# Nghich.net
KiCad netlist of a schematic drawn in Altium Designer
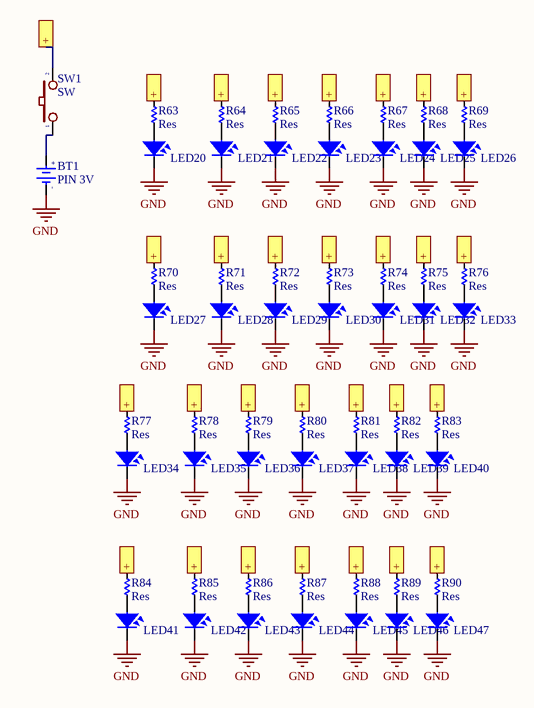
[diagram p0: Nghich.SchDoc]

(export (version "E")
  (design (tool "Eeschema 10.0.6"))
  (components
    (comp (ref "BT1")
      (value "PIN 3V")
      (footprint "PIN3V")
      (description "Battery 3VDC")
      (libsource (lib "LIBRARY") (part "PIN 3V"))
    )
    (comp (ref "LED20")
      (value "LED")
      (footprint "LED-0805-Blue")
      (libsource (lib "LIBRARY") (part "LED SMD"))
    )
    (comp (ref "LED21")
      (value "LED")
      (footprint "LED-0805-Blue")
      (libsource (lib "LIBRARY") (part "LED SMD"))
    )
    (comp (ref "LED22")
      (value "LED")
      (footprint "LED-0805-Blue")
      (libsource (lib "LIBRARY") (part "LED SMD"))
    )
    (comp (ref "LED23")
      (value "LED")
      (footprint "LED-0805-Blue")
      (libsource (lib "LIBRARY") (part "LED SMD"))
    )
    (comp (ref "LED24")
      (value "LED")
      (footprint "LED-0805-Blue")
      (libsource (lib "LIBRARY") (part "LED SMD"))
    )
    (comp (ref "LED25")
      (value "LED")
      (footprint "LED-0805-Blue")
      (libsource (lib "LIBRARY") (part "LED SMD"))
    )
    (comp (ref "LED26")
      (value "LED")
      (footprint "LED-0805-Blue")
      (libsource (lib "LIBRARY") (part "LED SMD"))
    )
    (comp (ref "LED27")
      (value "LED")
      (footprint "LED-0805-Blue")
      (libsource (lib "LIBRARY") (part "LED SMD"))
    )
    (comp (ref "LED28")
      (value "LED")
      (footprint "LED-0805-Blue")
      (libsource (lib "LIBRARY") (part "LED SMD"))
    )
    (comp (ref "LED29")
      (value "LED")
      (footprint "LED-0805-Blue")
      (libsource (lib "LIBRARY") (part "LED SMD"))
    )
    (comp (ref "LED30")
      (value "LED")
      (footprint "LED-0805-Blue")
      (libsource (lib "LIBRARY") (part "LED SMD"))
    )
    (comp (ref "LED31")
      (value "LED")
      (footprint "LED-0805-Blue")
      (libsource (lib "LIBRARY") (part "LED SMD"))
    )
    (comp (ref "LED32")
      (value "LED")
      (footprint "LED-0805-Blue")
      (libsource (lib "LIBRARY") (part "LED SMD"))
    )
    (comp (ref "LED33")
      (value "LED")
      (footprint "LED-0805-Blue")
      (libsource (lib "LIBRARY") (part "LED SMD"))
    )
    (comp (ref "LED34")
      (value "LED")
      (footprint "LED-0805-Blue")
      (libsource (lib "LIBRARY") (part "LED SMD"))
    )
    (comp (ref "LED35")
      (value "LED")
      (footprint "LED-0805-Blue")
      (libsource (lib "LIBRARY") (part "LED SMD"))
    )
    (comp (ref "LED36")
      (value "LED")
      (footprint "LED-0805-Blue")
      (libsource (lib "LIBRARY") (part "LED SMD"))
    )
    (comp (ref "LED37")
      (value "LED")
      (footprint "LED-0805-Blue")
      (libsource (lib "LIBRARY") (part "LED SMD"))
    )
    (comp (ref "LED38")
      (value "LED")
      (footprint "LED-0805-Blue")
      (libsource (lib "LIBRARY") (part "LED SMD"))
    )
    (comp (ref "LED39")
      (value "LED")
      (footprint "LED-0805-Blue")
      (libsource (lib "LIBRARY") (part "LED SMD"))
    )
    (comp (ref "LED40")
      (value "LED")
      (footprint "LED-0805-Blue")
      (libsource (lib "LIBRARY") (part "LED SMD"))
    )
    (comp (ref "LED41")
      (value "LED")
      (footprint "LED-0805-Blue")
      (libsource (lib "LIBRARY") (part "LED SMD"))
    )
    (comp (ref "LED42")
      (value "LED")
      (footprint "LED-0805-Blue")
      (libsource (lib "LIBRARY") (part "LED SMD"))
    )
    (comp (ref "LED43")
      (value "LED")
      (footprint "LED-0805-Blue")
      (libsource (lib "LIBRARY") (part "LED SMD"))
    )
    (comp (ref "LED44")
      (value "LED")
      (footprint "LED-0805-Blue")
      (libsource (lib "LIBRARY") (part "LED SMD"))
    )
    (comp (ref "LED45")
      (value "LED")
      (footprint "LED-0805-Blue")
      (libsource (lib "LIBRARY") (part "LED SMD"))
    )
    (comp (ref "LED46")
      (value "LED")
      (footprint "LED-0805-Blue")
      (libsource (lib "LIBRARY") (part "LED SMD"))
    )
    (comp (ref "LED47")
      (value "LED")
      (footprint "LED-0805-Blue")
      (libsource (lib "LIBRARY") (part "LED SMD"))
    )
    (comp (ref "R63")
      (value "Res")
      (footprint "RES-SMD-0805")
      (description "Resistor")
      (fields
        (field (name "MANUFACTURER") "Generic Components")
        (field (name "PUBLISHER") "Altium Hobart Technology Centre")
      )
      (libsource (lib "LIBRARY") (part "Res-SMD"))
    )
    (comp (ref "R64")
      (value "Res")
      (footprint "RES-SMD-0805")
      (description "Resistor")
      (fields
        (field (name "MANUFACTURER") "Generic Components")
        (field (name "PUBLISHER") "Altium Hobart Technology Centre")
      )
      (libsource (lib "LIBRARY") (part "Res-SMD"))
    )
    (comp (ref "R65")
      (value "Res")
      (footprint "RES-SMD-0805")
      (description "Resistor")
      (fields
        (field (name "MANUFACTURER") "Generic Components")
        (field (name "PUBLISHER") "Altium Hobart Technology Centre")
      )
      (libsource (lib "LIBRARY") (part "Res-SMD"))
    )
    (comp (ref "R66")
      (value "Res")
      (footprint "RES-SMD-0805")
      (description "Resistor")
      (fields
        (field (name "MANUFACTURER") "Generic Components")
        (field (name "PUBLISHER") "Altium Hobart Technology Centre")
      )
      (libsource (lib "LIBRARY") (part "Res-SMD"))
    )
    (comp (ref "R67")
      (value "Res")
      (footprint "RES-SMD-0805")
      (description "Resistor")
      (fields
        (field (name "MANUFACTURER") "Generic Components")
        (field (name "PUBLISHER") "Altium Hobart Technology Centre")
      )
      (libsource (lib "LIBRARY") (part "Res-SMD"))
    )
    (comp (ref "R68")
      (value "Res")
      (footprint "RES-SMD-0805")
      (description "Resistor")
      (fields
        (field (name "MANUFACTURER") "Generic Components")
        (field (name "PUBLISHER") "Altium Hobart Technology Centre")
      )
      (libsource (lib "LIBRARY") (part "Res-SMD"))
    )
    (comp (ref "R69")
      (value "Res")
      (footprint "RES-SMD-0805")
      (description "Resistor")
      (fields
        (field (name "MANUFACTURER") "Generic Components")
        (field (name "PUBLISHER") "Altium Hobart Technology Centre")
      )
      (libsource (lib "LIBRARY") (part "Res-SMD"))
    )
    (comp (ref "R70")
      (value "Res")
      (footprint "RES-SMD-0805")
      (description "Resistor")
      (fields
        (field (name "MANUFACTURER") "Generic Components")
        (field (name "PUBLISHER") "Altium Hobart Technology Centre")
      )
      (libsource (lib "LIBRARY") (part "Res-SMD"))
    )
    (comp (ref "R71")
      (value "Res")
      (footprint "RES-SMD-0805")
      (description "Resistor")
      (fields
        (field (name "MANUFACTURER") "Generic Components")
        (field (name "PUBLISHER") "Altium Hobart Technology Centre")
      )
      (libsource (lib "LIBRARY") (part "Res-SMD"))
    )
    (comp (ref "R72")
      (value "Res")
      (footprint "RES-SMD-0805")
      (description "Resistor")
      (fields
        (field (name "MANUFACTURER") "Generic Components")
        (field (name "PUBLISHER") "Altium Hobart Technology Centre")
      )
      (libsource (lib "LIBRARY") (part "Res-SMD"))
    )
    (comp (ref "R73")
      (value "Res")
      (footprint "RES-SMD-0805")
      (description "Resistor")
      (fields
        (field (name "MANUFACTURER") "Generic Components")
        (field (name "PUBLISHER") "Altium Hobart Technology Centre")
      )
      (libsource (lib "LIBRARY") (part "Res-SMD"))
    )
    (comp (ref "R74")
      (value "Res")
      (footprint "RES-SMD-0805")
      (description "Resistor")
      (fields
        (field (name "MANUFACTURER") "Generic Components")
        (field (name "PUBLISHER") "Altium Hobart Technology Centre")
      )
      (libsource (lib "LIBRARY") (part "Res-SMD"))
    )
    (comp (ref "R75")
      (value "Res")
      (footprint "RES-SMD-0805")
      (description "Resistor")
      (fields
        (field (name "MANUFACTURER") "Generic Components")
        (field (name "PUBLISHER") "Altium Hobart Technology Centre")
      )
      (libsource (lib "LIBRARY") (part "Res-SMD"))
    )
    (comp (ref "R76")
      (value "Res")
      (footprint "RES-SMD-0805")
      (description "Resistor")
      (fields
        (field (name "MANUFACTURER") "Generic Components")
        (field (name "PUBLISHER") "Altium Hobart Technology Centre")
      )
      (libsource (lib "LIBRARY") (part "Res-SMD"))
    )
    (comp (ref "R77")
      (value "Res")
      (footprint "RES-SMD-0805")
      (description "Resistor")
      (fields
        (field (name "MANUFACTURER") "Generic Components")
        (field (name "PUBLISHER") "Altium Hobart Technology Centre")
      )
      (libsource (lib "LIBRARY") (part "Res-SMD"))
    )
    (comp (ref "R78")
      (value "Res")
      (footprint "RES-SMD-0805")
      (description "Resistor")
      (fields
        (field (name "MANUFACTURER") "Generic Components")
        (field (name "PUBLISHER") "Altium Hobart Technology Centre")
      )
      (libsource (lib "LIBRARY") (part "Res-SMD"))
    )
    (comp (ref "R79")
      (value "Res")
      (footprint "RES-SMD-0805")
      (description "Resistor")
      (fields
        (field (name "MANUFACTURER") "Generic Components")
        (field (name "PUBLISHER") "Altium Hobart Technology Centre")
      )
      (libsource (lib "LIBRARY") (part "Res-SMD"))
    )
    (comp (ref "R80")
      (value "Res")
      (footprint "RES-SMD-0805")
      (description "Resistor")
      (fields
        (field (name "MANUFACTURER") "Generic Components")
        (field (name "PUBLISHER") "Altium Hobart Technology Centre")
      )
      (libsource (lib "LIBRARY") (part "Res-SMD"))
    )
    (comp (ref "R81")
      (value "Res")
      (footprint "RES-SMD-0805")
      (description "Resistor")
      (fields
        (field (name "MANUFACTURER") "Generic Components")
        (field (name "PUBLISHER") "Altium Hobart Technology Centre")
      )
      (libsource (lib "LIBRARY") (part "Res-SMD"))
    )
    (comp (ref "R82")
      (value "Res")
      (footprint "RES-SMD-0805")
      (description "Resistor")
      (fields
        (field (name "MANUFACTURER") "Generic Components")
        (field (name "PUBLISHER") "Altium Hobart Technology Centre")
      )
      (libsource (lib "LIBRARY") (part "Res-SMD"))
    )
    (comp (ref "R83")
      (value "Res")
      (footprint "RES-SMD-0805")
      (description "Resistor")
      (fields
        (field (name "MANUFACTURER") "Generic Components")
        (field (name "PUBLISHER") "Altium Hobart Technology Centre")
      )
      (libsource (lib "LIBRARY") (part "Res-SMD"))
    )
    (comp (ref "R84")
      (value "Res")
      (footprint "RES-SMD-0805")
      (description "Resistor")
      (fields
        (field (name "MANUFACTURER") "Generic Components")
        (field (name "PUBLISHER") "Altium Hobart Technology Centre")
      )
      (libsource (lib "LIBRARY") (part "Res-SMD"))
    )
    (comp (ref "R85")
      (value "Res")
      (footprint "RES-SMD-0805")
      (description "Resistor")
      (fields
        (field (name "MANUFACTURER") "Generic Components")
        (field (name "PUBLISHER") "Altium Hobart Technology Centre")
      )
      (libsource (lib "LIBRARY") (part "Res-SMD"))
    )
    (comp (ref "R86")
      (value "Res")
      (footprint "RES-SMD-0805")
      (description "Resistor")
      (fields
        (field (name "MANUFACTURER") "Generic Components")
        (field (name "PUBLISHER") "Altium Hobart Technology Centre")
      )
      (libsource (lib "LIBRARY") (part "Res-SMD"))
    )
    (comp (ref "R87")
      (value "Res")
      (footprint "RES-SMD-0805")
      (description "Resistor")
      (fields
        (field (name "MANUFACTURER") "Generic Components")
        (field (name "PUBLISHER") "Altium Hobart Technology Centre")
      )
      (libsource (lib "LIBRARY") (part "Res-SMD"))
    )
    (comp (ref "R88")
      (value "Res")
      (footprint "RES-SMD-0805")
      (description "Resistor")
      (fields
        (field (name "MANUFACTURER") "Generic Components")
        (field (name "PUBLISHER") "Altium Hobart Technology Centre")
      )
      (libsource (lib "LIBRARY") (part "Res-SMD"))
    )
    (comp (ref "R89")
      (value "Res")
      (footprint "RES-SMD-0805")
      (description "Resistor")
      (fields
        (field (name "MANUFACTURER") "Generic Components")
        (field (name "PUBLISHER") "Altium Hobart Technology Centre")
      )
      (libsource (lib "LIBRARY") (part "Res-SMD"))
    )
    (comp (ref "R90")
      (value "Res")
      (footprint "RES-SMD-0805")
      (description "Resistor")
      (fields
        (field (name "MANUFACTURER") "Generic Components")
        (field (name "PUBLISHER") "Altium Hobart Technology Centre")
      )
      (libsource (lib "LIBRARY") (part "Res-SMD"))
    )
    (comp (ref "SW1")
      (value "SW")
      (footprint "SW-DIP1")
      (description "Switch button 2 pin")
      (libsource (lib "LIBRARY") (part "SW2"))
    )
  )
  (nets
    (net (code "1") (name "/+") (class "Default")
      (node (ref "R63") (pin "1") (pinfunction "1_1") (pintype "passive"))
      (node (ref "R64") (pin "1") (pinfunction "1_1") (pintype "passive"))
      (node (ref "R65") (pin "1") (pinfunction "1_1") (pintype "passive"))
      (node (ref "R66") (pin "1") (pinfunction "1_1") (pintype "passive"))
      (node (ref "R67") (pin "1") (pinfunction "1_1") (pintype "passive"))
      (node (ref "R68") (pin "1") (pinfunction "1_1") (pintype "passive"))
      (node (ref "R69") (pin "1") (pinfunction "1_1") (pintype "passive"))
      (node (ref "R70") (pin "1") (pinfunction "1_1") (pintype "passive"))
      (node (ref "R71") (pin "1") (pinfunction "1_1") (pintype "passive"))
      (node (ref "R72") (pin "1") (pinfunction "1_1") (pintype "passive"))
      (node (ref "R73") (pin "1") (pinfunction "1_1") (pintype "passive"))
      (node (ref "R74") (pin "1") (pinfunction "1_1") (pintype "passive"))
      (node (ref "R75") (pin "1") (pinfunction "1_1") (pintype "passive"))
      (node (ref "R76") (pin "1") (pinfunction "1_1") (pintype "passive"))
      (node (ref "R77") (pin "1") (pinfunction "1_1") (pintype "passive"))
      (node (ref "R78") (pin "1") (pinfunction "1_1") (pintype "passive"))
      (node (ref "R79") (pin "1") (pinfunction "1_1") (pintype "passive"))
      (node (ref "R80") (pin "1") (pinfunction "1_1") (pintype "passive"))
      (node (ref "R81") (pin "1") (pinfunction "1_1") (pintype "passive"))
      (node (ref "R82") (pin "1") (pinfunction "1_1") (pintype "passive"))
      (node (ref "R83") (pin "1") (pinfunction "1_1") (pintype "passive"))
      (node (ref "R84") (pin "1") (pinfunction "1_1") (pintype "passive"))
      (node (ref "R85") (pin "1") (pinfunction "1_1") (pintype "passive"))
      (node (ref "R86") (pin "1") (pinfunction "1_1") (pintype "passive"))
      (node (ref "R87") (pin "1") (pinfunction "1_1") (pintype "passive"))
      (node (ref "R88") (pin "1") (pinfunction "1_1") (pintype "passive"))
      (node (ref "R89") (pin "1") (pinfunction "1_1") (pintype "passive"))
      (node (ref "R90") (pin "1") (pinfunction "1_1") (pintype "passive"))
      (node (ref "SW1") (pin "2") (pinfunction "2_2") (pintype "passive"))
    )
    (net (code "2") (name "GND") (class "Default")
      (node (ref "BT1") (pin "2") (pinfunction "GND_2") (pintype "passive"))
      (node (ref "LED20") (pin "2") (pinfunction "2_2") (pintype "passive"))
      (node (ref "LED21") (pin "2") (pinfunction "2_2") (pintype "passive"))
      (node (ref "LED22") (pin "2") (pinfunction "2_2") (pintype "passive"))
      (node (ref "LED23") (pin "2") (pinfunction "2_2") (pintype "passive"))
      (node (ref "LED24") (pin "2") (pinfunction "2_2") (pintype "passive"))
      (node (ref "LED25") (pin "2") (pinfunction "2_2") (pintype "passive"))
      (node (ref "LED26") (pin "2") (pinfunction "2_2") (pintype "passive"))
      (node (ref "LED27") (pin "2") (pinfunction "2_2") (pintype "passive"))
      (node (ref "LED28") (pin "2") (pinfunction "2_2") (pintype "passive"))
      (node (ref "LED29") (pin "2") (pinfunction "2_2") (pintype "passive"))
      (node (ref "LED30") (pin "2") (pinfunction "2_2") (pintype "passive"))
      (node (ref "LED31") (pin "2") (pinfunction "2_2") (pintype "passive"))
      (node (ref "LED32") (pin "2") (pinfunction "2_2") (pintype "passive"))
      (node (ref "LED33") (pin "2") (pinfunction "2_2") (pintype "passive"))
      (node (ref "LED34") (pin "2") (pinfunction "2_2") (pintype "passive"))
      (node (ref "LED35") (pin "2") (pinfunction "2_2") (pintype "passive"))
      (node (ref "LED36") (pin "2") (pinfunction "2_2") (pintype "passive"))
      (node (ref "LED37") (pin "2") (pinfunction "2_2") (pintype "passive"))
      (node (ref "LED38") (pin "2") (pinfunction "2_2") (pintype "passive"))
      (node (ref "LED39") (pin "2") (pinfunction "2_2") (pintype "passive"))
      (node (ref "LED40") (pin "2") (pinfunction "2_2") (pintype "passive"))
      (node (ref "LED41") (pin "2") (pinfunction "2_2") (pintype "passive"))
      (node (ref "LED42") (pin "2") (pinfunction "2_2") (pintype "passive"))
      (node (ref "LED43") (pin "2") (pinfunction "2_2") (pintype "passive"))
      (node (ref "LED44") (pin "2") (pinfunction "2_2") (pintype "passive"))
      (node (ref "LED45") (pin "2") (pinfunction "2_2") (pintype "passive"))
      (node (ref "LED46") (pin "2") (pinfunction "2_2") (pintype "passive"))
      (node (ref "LED47") (pin "2") (pinfunction "2_2") (pintype "passive"))
    )
    (net (code "3") (name "Net-(BT1-+3V)") (class "Default")
      (node (ref "BT1") (pin "1") (pinfunction "+3V_1") (pintype "passive"))
      (node (ref "SW1") (pin "1") (pinfunction "1_1") (pintype "passive"))
    )
    (net (code "4") (name "Net-(LED20-Pad1)") (class "Default")
      (node (ref "LED20") (pin "1") (pinfunction "1_1") (pintype "passive"))
      (node (ref "R63") (pin "2") (pinfunction "2_2") (pintype "passive"))
    )
    (net (code "5") (name "Net-(LED21-Pad1)") (class "Default")
      (node (ref "LED21") (pin "1") (pinfunction "1_1") (pintype "passive"))
      (node (ref "R64") (pin "2") (pinfunction "2_2") (pintype "passive"))
    )
    (net (code "6") (name "Net-(LED22-Pad1)") (class "Default")
      (node (ref "LED22") (pin "1") (pinfunction "1_1") (pintype "passive"))
      (node (ref "R65") (pin "2") (pinfunction "2_2") (pintype "passive"))
    )
    (net (code "7") (name "Net-(LED23-Pad1)") (class "Default")
      (node (ref "LED23") (pin "1") (pinfunction "1_1") (pintype "passive"))
      (node (ref "R66") (pin "2") (pinfunction "2_2") (pintype "passive"))
    )
    (net (code "8") (name "Net-(LED24-Pad1)") (class "Default")
      (node (ref "LED24") (pin "1") (pinfunction "1_1") (pintype "passive"))
      (node (ref "R67") (pin "2") (pinfunction "2_2") (pintype "passive"))
    )
    (net (code "9") (name "Net-(LED25-Pad1)") (class "Default")
      (node (ref "LED25") (pin "1") (pinfunction "1_1") (pintype "passive"))
      (node (ref "R68") (pin "2") (pinfunction "2_2") (pintype "passive"))
    )
    (net (code "10") (name "Net-(LED26-Pad1)") (class "Default")
      (node (ref "LED26") (pin "1") (pinfunction "1_1") (pintype "passive"))
      (node (ref "R69") (pin "2") (pinfunction "2_2") (pintype "passive"))
    )
    (net (code "11") (name "Net-(LED27-Pad1)") (class "Default")
      (node (ref "LED27") (pin "1") (pinfunction "1_1") (pintype "passive"))
      (node (ref "R70") (pin "2") (pinfunction "2_2") (pintype "passive"))
    )
    (net (code "12") (name "Net-(LED28-Pad1)") (class "Default")
      (node (ref "LED28") (pin "1") (pinfunction "1_1") (pintype "passive"))
      (node (ref "R71") (pin "2") (pinfunction "2_2") (pintype "passive"))
    )
    (net (code "13") (name "Net-(LED29-Pad1)") (class "Default")
      (node (ref "LED29") (pin "1") (pinfunction "1_1") (pintype "passive"))
      (node (ref "R72") (pin "2") (pinfunction "2_2") (pintype "passive"))
    )
    (net (code "14") (name "Net-(LED30-Pad1)") (class "Default")
      (node (ref "LED30") (pin "1") (pinfunction "1_1") (pintype "passive"))
      (node (ref "R73") (pin "2") (pinfunction "2_2") (pintype "passive"))
    )
    (net (code "15") (name "Net-(LED31-Pad1)") (class "Default")
      (node (ref "LED31") (pin "1") (pinfunction "1_1") (pintype "passive"))
      (node (ref "R74") (pin "2") (pinfunction "2_2") (pintype "passive"))
    )
    (net (code "16") (name "Net-(LED32-Pad1)") (class "Default")
      (node (ref "LED32") (pin "1") (pinfunction "1_1") (pintype "passive"))
      (node (ref "R75") (pin "2") (pinfunction "2_2") (pintype "passive"))
    )
    (net (code "17") (name "Net-(LED33-Pad1)") (class "Default")
      (node (ref "LED33") (pin "1") (pinfunction "1_1") (pintype "passive"))
      (node (ref "R76") (pin "2") (pinfunction "2_2") (pintype "passive"))
    )
    (net (code "18") (name "Net-(LED34-Pad1)") (class "Default")
      (node (ref "LED34") (pin "1") (pinfunction "1_1") (pintype "passive"))
      (node (ref "R77") (pin "2") (pinfunction "2_2") (pintype "passive"))
    )
    (net (code "19") (name "Net-(LED35-Pad1)") (class "Default")
      (node (ref "LED35") (pin "1") (pinfunction "1_1") (pintype "passive"))
      (node (ref "R78") (pin "2") (pinfunction "2_2") (pintype "passive"))
    )
    (net (code "20") (name "Net-(LED36-Pad1)") (class "Default")
      (node (ref "LED36") (pin "1") (pinfunction "1_1") (pintype "passive"))
      (node (ref "R79") (pin "2") (pinfunction "2_2") (pintype "passive"))
    )
    (net (code "21") (name "Net-(LED37-Pad1)") (class "Default")
      (node (ref "LED37") (pin "1") (pinfunction "1_1") (pintype "passive"))
      (node (ref "R80") (pin "2") (pinfunction "2_2") (pintype "passive"))
    )
    (net (code "22") (name "Net-(LED38-Pad1)") (class "Default")
      (node (ref "LED38") (pin "1") (pinfunction "1_1") (pintype "passive"))
      (node (ref "R81") (pin "2") (pinfunction "2_2") (pintype "passive"))
    )
    (net (code "23") (name "Net-(LED39-Pad1)") (class "Default")
      (node (ref "LED39") (pin "1") (pinfunction "1_1") (pintype "passive"))
      (node (ref "R82") (pin "2") (pinfunction "2_2") (pintype "passive"))
    )
    (net (code "24") (name "Net-(LED40-Pad1)") (class "Default")
      (node (ref "LED40") (pin "1") (pinfunction "1_1") (pintype "passive"))
      (node (ref "R83") (pin "2") (pinfunction "2_2") (pintype "passive"))
    )
    (net (code "25") (name "Net-(LED41-Pad1)") (class "Default")
      (node (ref "LED41") (pin "1") (pinfunction "1_1") (pintype "passive"))
      (node (ref "R84") (pin "2") (pinfunction "2_2") (pintype "passive"))
    )
    (net (code "26") (name "Net-(LED42-Pad1)") (class "Default")
      (node (ref "LED42") (pin "1") (pinfunction "1_1") (pintype "passive"))
      (node (ref "R85") (pin "2") (pinfunction "2_2") (pintype "passive"))
    )
    (net (code "27") (name "Net-(LED43-Pad1)") (class "Default")
      (node (ref "LED43") (pin "1") (pinfunction "1_1") (pintype "passive"))
      (node (ref "R86") (pin "2") (pinfunction "2_2") (pintype "passive"))
    )
    (net (code "28") (name "Net-(LED44-Pad1)") (class "Default")
      (node (ref "LED44") (pin "1") (pinfunction "1_1") (pintype "passive"))
      (node (ref "R87") (pin "2") (pinfunction "2_2") (pintype "passive"))
    )
    (net (code "29") (name "Net-(LED45-Pad1)") (class "Default")
      (node (ref "LED45") (pin "1") (pinfunction "1_1") (pintype "passive"))
      (node (ref "R88") (pin "2") (pinfunction "2_2") (pintype "passive"))
    )
    (net (code "30") (name "Net-(LED46-Pad1)") (class "Default")
      (node (ref "LED46") (pin "1") (pinfunction "1_1") (pintype "passive"))
      (node (ref "R89") (pin "2") (pinfunction "2_2") (pintype "passive"))
    )
    (net (code "31") (name "Net-(LED47-Pad1)") (class "Default")
      (node (ref "LED47") (pin "1") (pinfunction "1_1") (pintype "passive"))
      (node (ref "R90") (pin "2") (pinfunction "2_2") (pintype "passive"))
    )
  )
)
